# 6106_RC522.net
KiCad netlist of a schematic drawn in Altium Designer
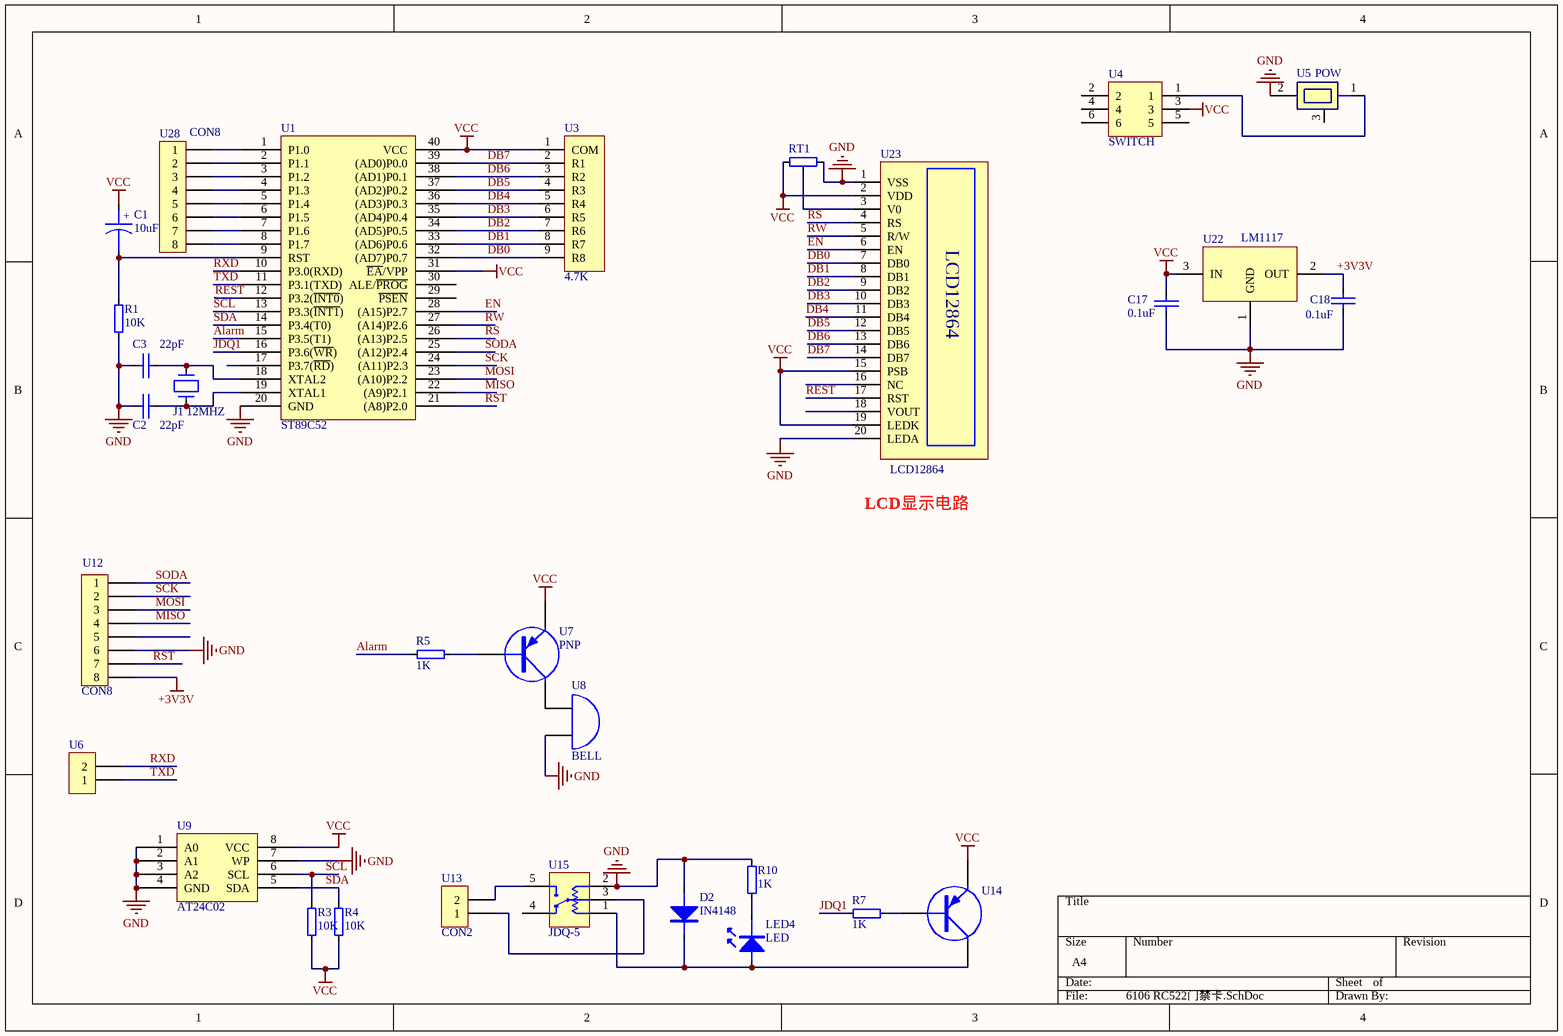
[diagram p0: 6106 RC522门禁卡.SchDoc]

(export (version "E")
  (design (tool "Eeschema 10.0.6"))
  (components
    (comp (ref "C1") (value "10uF") (footprint "C10") (libsource (lib "51SCH") (part "10uF")))
    (comp (ref "C2") (value "22pF") (footprint "CAP") (libsource (lib "51SCH") (part "0.1uF")))
    (comp (ref "C3") (value "22pF") (footprint "CAP") (libsource (lib "51SCH") (part "0.1uF")))
    (comp (ref "C17") (value "0.1uF") (footprint "CAP") (libsource (lib "51SCH") (part "0.1uF")))
    (comp (ref "C18") (value "0.1uF") (footprint "CAP") (libsource (lib "51SCH") (part "0.1uF")))
    (comp (ref "D2") (value "IN4148") (footprint "IN4148") (libsource (lib "51SCH") (part "DIODE")))
    (comp (ref "J1") (value "12MHZ") (footprint "CRYSTAL") (libsource (lib "51SCH") (part "CRYSTAL")))
    (comp (ref "LED4") (value "LED") (footprint "LED") (libsource (lib "51SCH") (part "LED")))
    (comp (ref "R1") (value "10K") (footprint "R-DIP") (libsource (lib "51SCH") (part "10K")))
    (comp (ref "R3") (value "10K") (footprint "R-DIP") (libsource (lib "51SCH") (part "1K")))
    (comp (ref "R4") (value "10K") (footprint "R-DIP") (libsource (lib "51SCH") (part "1K")))
    (comp (ref "R5") (value "1K") (footprint "R-DIP") (libsource (lib "51SCH") (part "1K")))
    (comp (ref "R7") (value "1K") (footprint "R-DIP") (libsource (lib "51SCH") (part "1K")))
    (comp (ref "R10") (value "1K") (footprint "R-DIP") (libsource (lib "51SCH") (part "1K")))
    (comp (ref "RT1") (value "~") (footprint "RT1") (libsource (lib "51SCH") (part "RT")))
    (comp (ref "U1") (value "ST89C52") (footprint "STC") (libsource (lib "51SCH") (part "STC51")))
    (comp (ref "U3") (value "4.7K") (footprint "SIP9") (libsource (lib "51SCH") (part "PAIZU")))
    (comp (ref "U4") (value "SWITCH") (footprint "SWITCH") (libsource (lib "51SCH") (part "SWITCH")))
    (comp (ref "U5") (value "POW") (footprint "DCM") (libsource (lib "51SCH") (part "POW")))
    (comp (ref "U6") (value "~") (footprint "SIP2") (libsource (lib "51SCH") (part "CON2")))
    (comp (ref "U7") (value "PNP") (footprint "PNP") (libsource (lib "51SCH") (part "PNP")))
    (comp (ref "U8") (value "BELL") (footprint "BEEP") (libsource (lib "51SCH") (part "BELL")))
    (comp (ref "U9") (value "AT24C02") (footprint "DIP8") (libsource (lib "51SCH") (part "AT24C02")))
    (comp (ref "U12") (value "CON8") (footprint "SIP8") (libsource (lib "Singlechip-51") (part "CON8")))
    (comp (ref "U13") (value "CON2") (footprint "SIP2") (libsource (lib "51SCH") (part "CON2")))
    (comp (ref "U14") (value "~") (footprint "PNP") (libsource (lib "51SCH") (part "PNP")))
    (comp (ref "U15") (value "JDQ-5") (footprint "JDQ-5") (libsource (lib "51SCH") (part "JDQ-5")))
    (comp (ref "U22") (value "LM1117") (footprint "7805") (libsource (lib "51SCH") (part "LM1117")))
    (comp (ref "U23") (value "LCD12864") (footprint "SIP20") (libsource (lib "51SCH") (part "LCD12864")))
    (comp (ref "U28") (value "CON8") (footprint "SIP8") (libsource (lib "Singlechip-51") (part "CON8")))
  )
  (nets
    (net (code "1") (name "+3V3V") (class "Default")
      (node (ref "C18") (pin "2") (pinfunction "2_2") (pintype "passive"))
      (node (ref "U12") (pin "8") (pinfunction "8_8") (pintype "passive"))
      (node (ref "U22") (pin "2") (pinfunction "OUT_2") (pintype "passive"))
    )
    (net (code "2") (name "/Alarm") (class "Default")
      (node (ref "R5") (pin "1") (pinfunction "1_1") (pintype "passive"))
      (node (ref "U1") (pin "15") (pinfunction "P3.5(T1)_15") (pintype "passive"))
    )
    (net (code "3") (name "/DB0") (class "Default")
      (node (ref "U1") (pin "32") (pinfunction "(AD7)P0.7_32") (pintype "passive"))
      (node (ref "U23") (pin "7") (pinfunction "DB0_7") (pintype "passive"))
      (node (ref "U3") (pin "9") (pinfunction "R8_9") (pintype "passive"))
    )
    (net (code "4") (name "/DB1") (class "Default")
      (node (ref "U1") (pin "33") (pinfunction "(AD6)P0.6_33") (pintype "passive"))
      (node (ref "U23") (pin "8") (pinfunction "DB1_8") (pintype "passive"))
      (node (ref "U3") (pin "8") (pinfunction "R7_8") (pintype "passive"))
    )
    (net (code "5") (name "/DB2") (class "Default")
      (node (ref "U1") (pin "34") (pinfunction "(AD5)P0.5_34") (pintype "passive"))
      (node (ref "U23") (pin "9") (pinfunction "DB2_9") (pintype "passive"))
      (node (ref "U3") (pin "7") (pinfunction "R6_7") (pintype "passive"))
    )
    (net (code "6") (name "/DB3") (class "Default")
      (node (ref "U1") (pin "35") (pinfunction "(AD4)P0.4_35") (pintype "passive"))
      (node (ref "U23") (pin "10") (pinfunction "DB3_10") (pintype "passive"))
      (node (ref "U3") (pin "6") (pinfunction "R5_6") (pintype "passive"))
    )
    (net (code "7") (name "/DB4") (class "Default")
      (node (ref "U1") (pin "36") (pinfunction "(AD3)P0.3_36") (pintype "passive"))
      (node (ref "U23") (pin "11") (pinfunction "DB4_11") (pintype "passive"))
      (node (ref "U3") (pin "5") (pinfunction "R4_5") (pintype "passive"))
    )
    (net (code "8") (name "/DB5") (class "Default")
      (node (ref "U1") (pin "37") (pinfunction "(AD2)P0.2_37") (pintype "passive"))
      (node (ref "U23") (pin "12") (pinfunction "DB5_12") (pintype "passive"))
      (node (ref "U3") (pin "4") (pinfunction "R3_4") (pintype "passive"))
    )
    (net (code "9") (name "/DB6") (class "Default")
      (node (ref "U1") (pin "38") (pinfunction "(AD1)P0.1_38") (pintype "passive"))
      (node (ref "U23") (pin "13") (pinfunction "DB6_13") (pintype "passive"))
      (node (ref "U3") (pin "3") (pinfunction "R2_3") (pintype "passive"))
    )
    (net (code "10") (name "/DB7") (class "Default")
      (node (ref "U1") (pin "39") (pinfunction "(AD0)P0.0_39") (pintype "passive"))
      (node (ref "U23") (pin "14") (pinfunction "DB7_14") (pintype "passive"))
      (node (ref "U3") (pin "2") (pinfunction "R1_2") (pintype "passive"))
    )
    (net (code "11") (name "/EN") (class "Default")
      (node (ref "U1") (pin "28") (pinfunction "(A15)P2.7_28") (pintype "passive"))
      (node (ref "U23") (pin "6") (pinfunction "EN_6") (pintype "passive"))
    )
    (net (code "12") (name "/JDQ1") (class "Default")
      (node (ref "R7") (pin "1") (pinfunction "1_1") (pintype "passive"))
      (node (ref "U1") (pin "16") (pinfunction "P3.6(~{WR})_16") (pintype "passive"))
    )
    (net (code "13") (name "/MISO") (class "Default")
      (node (ref "U1") (pin "22") (pinfunction "(A9)P2.1_22") (pintype "passive"))
      (node (ref "U12") (pin "4") (pinfunction "4_4") (pintype "passive"))
    )
    (net (code "14") (name "/MOSI") (class "Default")
      (node (ref "U1") (pin "23") (pinfunction "(A10)P2.2_23") (pintype "passive"))
      (node (ref "U12") (pin "3") (pinfunction "3_3") (pintype "passive"))
    )
    (net (code "15") (name "/REST") (class "Default")
      (node (ref "U1") (pin "12") (pinfunction "P3.2(~{INT0})_12") (pintype "passive"))
      (node (ref "U23") (pin "17") (pinfunction "RST_17") (pintype "passive"))
    )
    (net (code "16") (name "/RS") (class "Default")
      (node (ref "U1") (pin "26") (pinfunction "(A13)P2.5_26") (pintype "passive"))
      (node (ref "U23") (pin "4") (pinfunction "RS_4") (pintype "passive"))
    )
    (net (code "17") (name "/RST") (class "Default")
      (node (ref "U1") (pin "21") (pinfunction "(A8)P2.0_21") (pintype "passive"))
      (node (ref "U12") (pin "7") (pinfunction "7_7") (pintype "passive"))
    )
    (net (code "18") (name "/RW") (class "Default")
      (node (ref "U1") (pin "27") (pinfunction "(A14)P2.6_27") (pintype "passive"))
      (node (ref "U23") (pin "5") (pinfunction "R/W_5") (pintype "passive"))
    )
    (net (code "19") (name "/RXD") (class "Default")
      (node (ref "U1") (pin "10") (pinfunction "P3.0(RXD)_10") (pintype "passive"))
      (node (ref "U6") (pin "2") (pinfunction "2_2") (pintype "passive"))
    )
    (net (code "20") (name "/SCK") (class "Default")
      (node (ref "U1") (pin "24") (pinfunction "(A11)P2.3_24") (pintype "passive"))
      (node (ref "U12") (pin "2") (pinfunction "2_2") (pintype "passive"))
    )
    (net (code "21") (name "/SCL") (class "Default")
      (node (ref "R3") (pin "2") (pinfunction "2_2") (pintype "passive"))
      (node (ref "U1") (pin "13") (pinfunction "P3.3(~{INT1})_13") (pintype "passive"))
      (node (ref "U9") (pin "6") (pinfunction "SCL_6") (pintype "passive"))
    )
    (net (code "22") (name "/SDA") (class "Default")
      (node (ref "R4") (pin "2") (pinfunction "2_2") (pintype "passive"))
      (node (ref "U1") (pin "14") (pinfunction "P3.4(T0)_14") (pintype "passive"))
      (node (ref "U9") (pin "5") (pinfunction "SDA_5") (pintype "passive"))
    )
    (net (code "23") (name "/SODA") (class "Default")
      (node (ref "U1") (pin "25") (pinfunction "(A12)P2.4_25") (pintype "passive"))
      (node (ref "U12") (pin "1") (pinfunction "1_1") (pintype "passive"))
    )
    (net (code "24") (name "/TXD") (class "Default")
      (node (ref "U1") (pin "11") (pinfunction "P3.1(TXD)_11") (pintype "passive"))
      (node (ref "U6") (pin "1") (pinfunction "1_1") (pintype "passive"))
    )
    (net (code "25") (name "GND") (class "Default")
      (node (ref "C17") (pin "1") (pinfunction "1_1") (pintype "passive"))
      (node (ref "C18") (pin "1") (pinfunction "1_1") (pintype "passive"))
      (node (ref "C2") (pin "1") (pinfunction "1_1") (pintype "passive"))
      (node (ref "C3") (pin "1") (pinfunction "1_1") (pintype "passive"))
      (node (ref "D2") (pin "1") (pinfunction "A_1") (pintype "passive"))
      (node (ref "R1") (pin "2") (pinfunction "2_2") (pintype "passive"))
      (node (ref "R10") (pin "1") (pinfunction "1_1") (pintype "passive"))
      (node (ref "RT1") (pin "1") (pintype "passive"))
      (node (ref "U1") (pin "20") (pinfunction "GND_20") (pintype "passive"))
      (node (ref "U12") (pin "6") (pinfunction "6_6") (pintype "passive"))
      (node (ref "U15") (pin "2") (pintype "passive"))
      (node (ref "U22") (pin "1") (pinfunction "GND_1") (pintype "passive"))
      (node (ref "U23") (pin "1") (pinfunction "VSS_1") (pintype "passive"))
      (node (ref "U23") (pin "20") (pinfunction "LEDA_20") (pintype "passive"))
      (node (ref "U5") (pin "2") (pintype "passive"))
      (node (ref "U8") (pin "2") (pinfunction "B_2") (pintype "passive"))
      (node (ref "U9") (pin "1") (pinfunction "A0_1") (pintype "passive"))
      (node (ref "U9") (pin "2") (pinfunction "A1_2") (pintype "passive"))
      (node (ref "U9") (pin "3") (pinfunction "A2_3") (pintype "passive"))
      (node (ref "U9") (pin "4") (pinfunction "GND_4") (pintype "passive"))
      (node (ref "U9") (pin "7") (pinfunction "WP_7") (pintype "passive"))
    )
    (net (code "26") (name "Net-(D2-K)") (class "Default")
      (node (ref "D2") (pin "2") (pinfunction "K_2") (pintype "passive"))
      (node (ref "LED4") (pin "1") (pinfunction "1_1") (pintype "passive"))
      (node (ref "U14") (pin "3") (pinfunction "C_3") (pintype "passive"))
      (node (ref "U15") (pin "1") (pintype "passive"))
    )
    (net (code "27") (name "Net-(LED4-Pad2)") (class "Default")
      (node (ref "LED4") (pin "2") (pinfunction "2_2") (pintype "passive"))
      (node (ref "R10") (pin "2") (pinfunction "2_2") (pintype "passive"))
    )
    (net (code "28") (name "Net-(U1-P1.0)") (class "Default")
      (node (ref "U1") (pin "1") (pinfunction "P1.0_1") (pintype "passive"))
      (node (ref "U28") (pin "1") (pinfunction "1_1") (pintype "passive"))
    )
    (net (code "29") (name "Net-(U1-P1.1)") (class "Default")
      (node (ref "U1") (pin "2") (pinfunction "P1.1_2") (pintype "passive"))
      (node (ref "U28") (pin "2") (pinfunction "2_2") (pintype "passive"))
    )
    (net (code "30") (name "Net-(U1-P1.2)") (class "Default")
      (node (ref "U1") (pin "3") (pinfunction "P1.2_3") (pintype "passive"))
      (node (ref "U28") (pin "3") (pinfunction "3_3") (pintype "passive"))
    )
    (net (code "31") (name "Net-(U1-P1.3)") (class "Default")
      (node (ref "U1") (pin "4") (pinfunction "P1.3_4") (pintype "passive"))
      (node (ref "U28") (pin "4") (pinfunction "4_4") (pintype "passive"))
    )
    (net (code "32") (name "Net-(U1-P1.4)") (class "Default")
      (node (ref "U1") (pin "5") (pinfunction "P1.4_5") (pintype "passive"))
      (node (ref "U28") (pin "5") (pinfunction "5_5") (pintype "passive"))
    )
    (net (code "33") (name "Net-(U1-P1.5)") (class "Default")
      (node (ref "U1") (pin "6") (pinfunction "P1.5_6") (pintype "passive"))
      (node (ref "U28") (pin "6") (pinfunction "6_6") (pintype "passive"))
    )
    (net (code "34") (name "Net-(U1-P1.6)") (class "Default")
      (node (ref "U1") (pin "7") (pinfunction "P1.6_7") (pintype "passive"))
      (node (ref "U28") (pin "7") (pinfunction "7_7") (pintype "passive"))
    )
    (net (code "35") (name "Net-(U1-P1.7)") (class "Default")
      (node (ref "U1") (pin "8") (pinfunction "P1.7_8") (pintype "passive"))
      (node (ref "U28") (pin "8") (pinfunction "8_8") (pintype "passive"))
    )
    (net (code "36") (name "Net-(U1-RST)") (class "Default")
      (node (ref "C1") (pin "2") (pinfunction "2_2") (pintype "passive"))
      (node (ref "R1") (pin "1") (pinfunction "1_1") (pintype "passive"))
      (node (ref "U1") (pin "9") (pinfunction "RST_9") (pintype "passive"))
    )
    (net (code "37") (name "Net-(U1-XTAL1)") (class "Default")
      (node (ref "C3") (pin "2") (pinfunction "2_2") (pintype "passive"))
      (node (ref "J1") (pin "1") (pinfunction "1_1") (pintype "passive"))
      (node (ref "U1") (pin "19") (pinfunction "XTAL1_19") (pintype "passive"))
    )
    (net (code "38") (name "Net-(U1-XTAL2)") (class "Default")
      (node (ref "C2") (pin "2") (pinfunction "2_2") (pintype "passive"))
      (node (ref "J1") (pin "2") (pinfunction "2_2") (pintype "passive"))
      (node (ref "U1") (pin "18") (pinfunction "XTAL2_18") (pintype "passive"))
    )
    (net (code "39") (name "Net-(U4-Pad1)") (class "Default")
      (node (ref "U4") (pin "1") (pinfunction "1_1") (pintype "passive"))
      (node (ref "U5") (pin "1") (pintype "passive"))
    )
    (net (code "40") (name "Net-(U7-B)") (class "Default")
      (node (ref "R5") (pin "2") (pinfunction "2_2") (pintype "passive"))
      (node (ref "U7") (pin "1") (pinfunction "B_1") (pintype "passive"))
    )
    (net (code "41") (name "Net-(U7-C)") (class "Default")
      (node (ref "U7") (pin "3") (pinfunction "C_3") (pintype "passive"))
      (node (ref "U8") (pin "1") (pinfunction "A_1") (pintype "passive"))
    )
    (net (code "42") (name "Net-(U13-Pad1)") (class "Default")
      (node (ref "U13") (pin "1") (pinfunction "1_1") (pintype "passive"))
      (node (ref "U15") (pin "3") (pinfunction "IN_3") (pintype "passive"))
    )
    (net (code "43") (name "Net-(U13-Pad2)") (class "Default")
      (node (ref "U13") (pin "2") (pinfunction "2_2") (pintype "passive"))
      (node (ref "U15") (pin "5") (pinfunction "IN_5") (pintype "passive"))
    )
    (net (code "44") (name "Net-(U14-B)") (class "Default")
      (node (ref "R7") (pin "2") (pinfunction "2_2") (pintype "passive"))
      (node (ref "U14") (pin "1") (pinfunction "B_1") (pintype "passive"))
    )
    (net (code "45") (name "Net-(U23-V0)") (class "Default")
      (node (ref "RT1") (pin "3") (pintype "passive"))
      (node (ref "U23") (pin "3") (pinfunction "V0_3") (pintype "passive"))
    )
    (net (code "46") (name "VCC") (class "Default")
      (node (ref "C1") (pin "1") (pinfunction "1_1") (pintype "passive"))
      (node (ref "C17") (pin "2") (pinfunction "2_2") (pintype "passive"))
      (node (ref "R3") (pin "1") (pinfunction "1_1") (pintype "passive"))
      (node (ref "R4") (pin "1") (pinfunction "1_1") (pintype "passive"))
      (node (ref "RT1") (pin "2") (pintype "passive"))
      (node (ref "U1") (pin "31") (pinfunction "~{EA}/VPP_31") (pintype "passive"))
      (node (ref "U1") (pin "40") (pinfunction "VCC_40") (pintype "passive"))
      (node (ref "U14") (pin "2") (pinfunction "E_2") (pintype "passive"))
      (node (ref "U22") (pin "3") (pinfunction "IN_3") (pintype "passive"))
      (node (ref "U23") (pin "15") (pinfunction "PSB_15") (pintype "passive"))
      (node (ref "U23") (pin "19") (pinfunction "LEDK_19") (pintype "passive"))
      (node (ref "U23") (pin "2") (pinfunction "VDD_2") (pintype "passive"))
      (node (ref "U3") (pin "1") (pinfunction "COM_1") (pintype "passive"))
      (node (ref "U4") (pin "3") (pinfunction "3_3") (pintype "passive"))
      (node (ref "U7") (pin "2") (pinfunction "E_2") (pintype "passive"))
      (node (ref "U9") (pin "8") (pinfunction "VCC_8") (pintype "passive"))
    )
    (net (code "47") (name "unconnected-(U1-ALE{slash}~{PROG}-Pad30)") (class "Default")
      (node (ref "U1") (pin "30") (pinfunction "ALE/~{PROG}_30") (pintype "passive"))
    )
    (net (code "48") (name "unconnected-(U1-P3.7(~{RD})-Pad17)") (class "Default")
      (node (ref "U1") (pin "17") (pinfunction "P3.7(~{RD})_17") (pintype "passive"))
    )
    (net (code "49") (name "unconnected-(U1-~{PSEN}-Pad29)") (class "Default")
      (node (ref "U1") (pin "29") (pinfunction "~{PSEN}_29") (pintype "passive"))
    )
    (net (code "50") (name "unconnected-(U4-Pad2)") (class "Default")
      (node (ref "U4") (pin "2") (pinfunction "2_2") (pintype "passive"))
    )
    (net (code "51") (name "unconnected-(U4-Pad4)") (class "Default")
      (node (ref "U4") (pin "4") (pinfunction "4_4") (pintype "passive"))
    )
    (net (code "52") (name "unconnected-(U4-Pad5)") (class "Default")
      (node (ref "U4") (pin "5") (pinfunction "5_5") (pintype "passive"))
    )
    (net (code "53") (name "unconnected-(U4-Pad6)") (class "Default")
      (node (ref "U4") (pin "6") (pinfunction "6_6") (pintype "passive"))
    )
    (net (code "54") (name "unconnected-(U5-Pad3)") (class "Default")
      (node (ref "U5") (pin "3") (pintype "passive"))
    )
    (net (code "55") (name "unconnected-(U12-Pad5)") (class "Default")
      (node (ref "U12") (pin "5") (pinfunction "5_5") (pintype "passive"))
    )
    (net (code "56") (name "unconnected-(U15-IN-Pad4)") (class "Default")
      (node (ref "U15") (pin "4") (pinfunction "IN_4") (pintype "passive"))
    )
    (net (code "57") (name "unconnected-(U23-NC-Pad16)") (class "Default")
      (node (ref "U23") (pin "16") (pinfunction "NC_16") (pintype "passive"))
    )
    (net (code "58") (name "unconnected-(U23-VOUT-Pad18)") (class "Default")
      (node (ref "U23") (pin "18") (pinfunction "VOUT_18") (pintype "passive"))
    )
  )
)
